# receiver_mini_rfm95.net
KiCad netlist of a schematic drawn in EAGLE
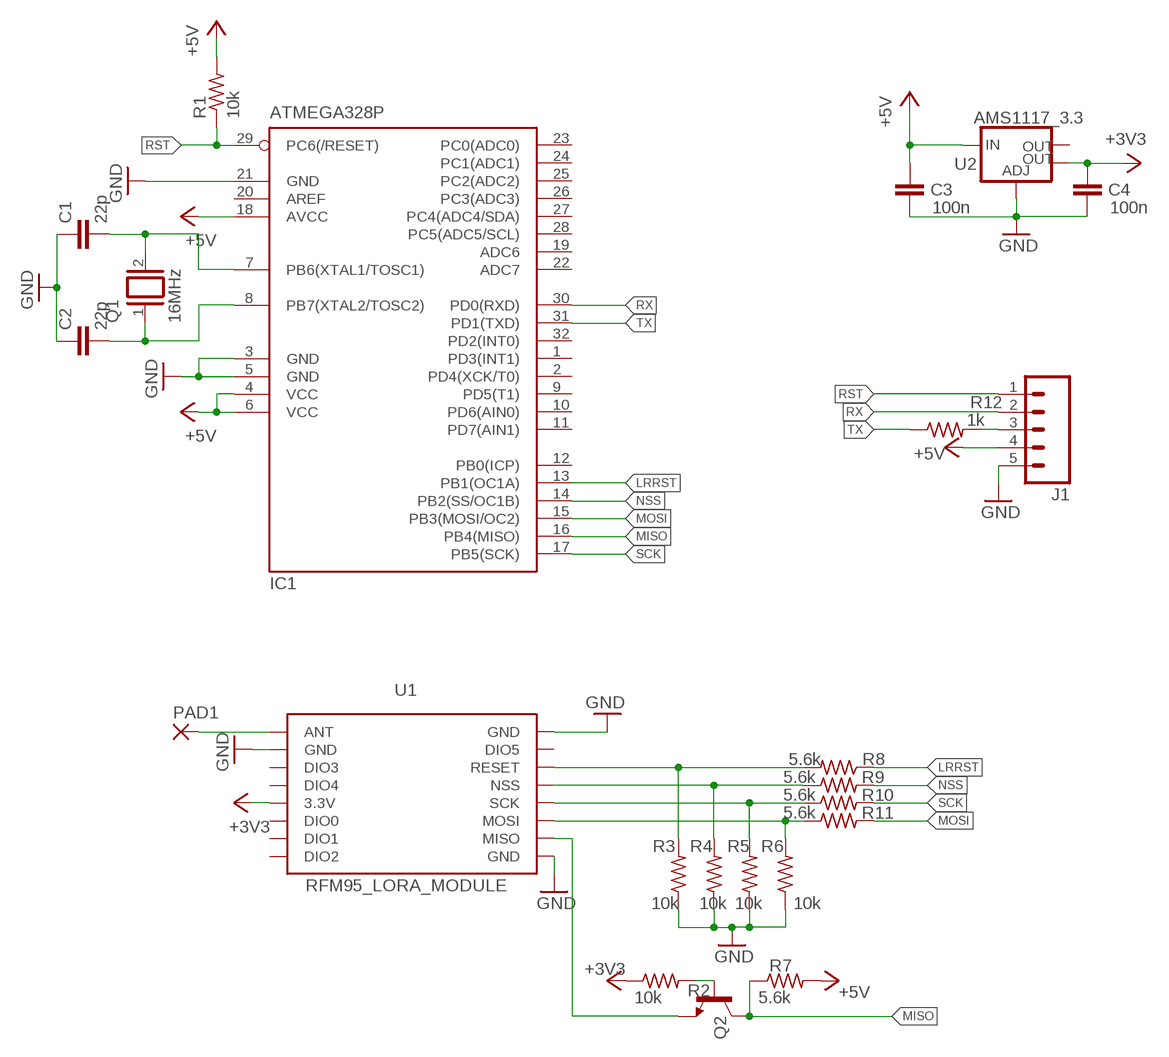
[diagram p0: schematic, sheet 1]

(export (version "E")
  (design (tool "Eeschema 10.0.6"))
  (components
    (comp (ref "C1")
      (value "22p")
      (footprint "eagle-import:C0805K")
      (libsource (lib "eagle-import") (part "C-EUC0805K"))
    )
    (comp (ref "C2")
      (value "22p")
      (footprint "eagle-import:C0805K")
      (libsource (lib "eagle-import") (part "C-EUC0805K"))
    )
    (comp (ref "C3")
      (value "100n")
      (footprint "eagle-import:C0805K")
      (libsource (lib "eagle-import") (part "C-EUC0805K"))
    )
    (comp (ref "C4")
      (value "100n")
      (footprint "eagle-import:C0805K")
      (libsource (lib "eagle-import") (part "C-EUC0805K"))
    )
    (comp (ref "IC1")
      (value "ATMEGA328P")
      (footprint "eagle-import:TQFP32-08")
      (fields (field (name "MPN") "ATMEGA8-16AU"))
      (libsource (lib "eagle-import") (part "MEGA8-AI"))
    )
    (comp (ref "J1")
      (value "M05PTH")
      (footprint "eagle-import:1X05")
      (libsource (lib "eagle-import") (part "M05PTH"))
    )
    (comp (ref "PAD1")
      (value "2,15/1,0")
      (footprint "eagle-import:2,15_1,0")
      (libsource (lib "eagle-import") (part "2,15/1,0"))
    )
    (comp (ref "Q1")
      (value "16MHz")
      (footprint "eagle-import:QS")
      (libsource (lib "eagle-import") (part "XTAL/S"))
    )
    (comp (ref "Q2")
      (value "BC817-16SMD")
      (footprint "eagle-import:SOT23-BEC")
      (libsource (lib "eagle-import") (part "BC817SMD-16"))
    )
    (comp (ref "R1")
      (value "10k")
      (footprint "eagle-import:R0805")
      (libsource (lib "eagle-import") (part "R-US_R0805"))
    )
    (comp (ref "R2")
      (value "10k")
      (footprint "eagle-import:R0805")
      (libsource (lib "eagle-import") (part "R-US_R0805"))
    )
    (comp (ref "R3")
      (value "10k")
      (footprint "eagle-import:R0805")
      (libsource (lib "eagle-import") (part "R-US_R0805"))
    )
    (comp (ref "R4")
      (value "10k")
      (footprint "eagle-import:R0805")
      (libsource (lib "eagle-import") (part "R-US_R0805"))
    )
    (comp (ref "R5")
      (value "10k")
      (footprint "eagle-import:R0805")
      (libsource (lib "eagle-import") (part "R-US_R0805"))
    )
    (comp (ref "R6")
      (value "10k")
      (footprint "eagle-import:R0805")
      (libsource (lib "eagle-import") (part "R-US_R0805"))
    )
    (comp (ref "R7")
      (value "5.6k")
      (footprint "eagle-import:R0805")
      (libsource (lib "eagle-import") (part "R-US_R0805"))
    )
    (comp (ref "R8")
      (value "5.6k")
      (footprint "eagle-import:R0805")
      (libsource (lib "eagle-import") (part "R-US_R0805"))
    )
    (comp (ref "R9")
      (value "5.6k")
      (footprint "eagle-import:R0805")
      (libsource (lib "eagle-import") (part "R-US_R0805"))
    )
    (comp (ref "R10")
      (value "5.6k")
      (footprint "eagle-import:R0805")
      (libsource (lib "eagle-import") (part "R-US_R0805"))
    )
    (comp (ref "R11")
      (value "5.6k")
      (footprint "eagle-import:R0805")
      (libsource (lib "eagle-import") (part "R-US_R0805"))
    )
    (comp (ref "R12")
      (value "1k")
      (footprint "eagle-import:R0805")
      (libsource (lib "eagle-import") (part "R-US_R0805"))
    )
    (comp (ref "U1")
      (value "RFM95_LORA_MODULE")
      (footprint "eagle-import:RFM95")
      (libsource (lib "eagle-import") (part "RFM95_LORA_MODULE"))
    )
    (comp (ref "U2")
      (value "AMS1117_3.3")
      (footprint "eagle-import:SOT223")
      (libsource (lib "eagle-import") (part "V_REG_LM1117SOT223"))
    )
  )
  (nets
    (net (code "1") (name "+3V3") (class "Default")
      (node (ref "C4") (pin "2") (pinfunction "2_2") (pintype "passive"))
      (node (ref "R2") (pin "1") (pinfunction "1_1") (pintype "passive"))
      (node (ref "U1") (pin "3.3V") (pinfunction "3.3V_3.3V") (pintype "bidirectional"))
      (node (ref "U2") (pin "4") (pinfunction "OUT_4") (pintype "output"))
    )
    (net (code "2") (name "+5V") (class "Default")
      (node (ref "C3") (pin "2") (pinfunction "2_2") (pintype "passive"))
      (node (ref "IC1") (pin "18") (pinfunction "AVCC_18") (pintype "power_in"))
      (node (ref "IC1") (pin "4") (pinfunction "VCC_4") (pintype "power_in"))
      (node (ref "IC1") (pin "6") (pinfunction "VCC_6") (pintype "power_in"))
      (node (ref "J1") (pin "4") (pinfunction "4_4") (pintype "passive"))
      (node (ref "R1") (pin "2") (pinfunction "2_2") (pintype "passive"))
      (node (ref "R7") (pin "2") (pinfunction "2_2") (pintype "passive"))
      (node (ref "U2") (pin "3") (pinfunction "IN_3") (pintype "input"))
    )
    (net (code "3") (name "/DIO3") (class "Default")
      (node (ref "U1") (pin "DIO3") (pinfunction "DIO3_DIO3") (pintype "power_in"))
    )
    (net (code "4") (name "GND") (class "Default")
      (node (ref "C1") (pin "1") (pinfunction "1_1") (pintype "passive"))
      (node (ref "C2") (pin "1") (pinfunction "1_1") (pintype "passive"))
      (node (ref "C3") (pin "1") (pinfunction "1_1") (pintype "passive"))
      (node (ref "C4") (pin "1") (pinfunction "1_1") (pintype "passive"))
      (node (ref "IC1") (pin "21") (pinfunction "GND_21") (pintype "power_in"))
      (node (ref "IC1") (pin "3") (pinfunction "GND_3") (pintype "power_in"))
      (node (ref "IC1") (pin "5") (pinfunction "GND_5") (pintype "power_in"))
      (node (ref "J1") (pin "5") (pinfunction "5_5") (pintype "passive"))
      (node (ref "R3") (pin "1") (pinfunction "1_1") (pintype "passive"))
      (node (ref "R4") (pin "1") (pinfunction "1_1") (pintype "passive"))
      (node (ref "R5") (pin "1") (pinfunction "1_1") (pintype "passive"))
      (node (ref "R6") (pin "1") (pinfunction "1_1") (pintype "passive"))
      (node (ref "U1") (pin "GND") (pinfunction "GND_GND") (pintype "power_in"))
      (node (ref "U1") (pin "GND@1") (pinfunction "GND_GND@1") (pintype "power_in"))
      (node (ref "U1") (pin "GND@2") (pinfunction "GND_GND@2") (pintype "power_in"))
      (node (ref "U2") (pin "1") (pinfunction "ADJ_1") (pintype "input"))
    )
    (net (code "5") (name "LRRST") (class "Default")
      (node (ref "IC1") (pin "13") (pinfunction "PB1(OC1A)_13") (pintype "bidirectional"))
      (node (ref "R8") (pin "1") (pinfunction "1_1") (pintype "passive"))
    )
    (net (code "6") (name "MISO") (class "Default")
      (node (ref "IC1") (pin "16") (pinfunction "PB4(MISO)_16") (pintype "bidirectional"))
      (node (ref "Q2") (pin "C") (pinfunction "C_C") (pintype "passive"))
      (node (ref "R7") (pin "1") (pinfunction "1_1") (pintype "passive"))
    )
    (net (code "7") (name "MOSI") (class "Default")
      (node (ref "IC1") (pin "15") (pinfunction "PB3(MOSI/OC2)_15") (pintype "bidirectional"))
      (node (ref "R11") (pin "2") (pinfunction "2_2") (pintype "passive"))
    )
    (net (code "8") (name "NSS") (class "Default")
      (node (ref "IC1") (pin "14") (pinfunction "PB2(SS/OC1B)_14") (pintype "bidirectional"))
      (node (ref "R9") (pin "2") (pinfunction "2_2") (pintype "passive"))
    )
    (net (code "9") (name "Net-(IC1-PB6(XTAL1{slash}TOSC1))") (class "Default")
      (node (ref "C1") (pin "2") (pinfunction "2_2") (pintype "passive"))
      (node (ref "IC1") (pin "7") (pinfunction "PB6(XTAL1/TOSC1)_7") (pintype "bidirectional"))
      (node (ref "Q1") (pin "2") (pinfunction "2_2") (pintype "passive"))
    )
    (net (code "10") (name "Net-(IC1-PB7(XTAL2{slash}TOSC2))") (class "Default")
      (node (ref "C2") (pin "2") (pinfunction "2_2") (pintype "passive"))
      (node (ref "IC1") (pin "8") (pinfunction "PB7(XTAL2/TOSC2)_8") (pintype "bidirectional"))
      (node (ref "Q1") (pin "1") (pinfunction "1_1") (pintype "passive"))
    )
    (net (code "11") (name "Net-(J1-Pad3)") (class "Default")
      (node (ref "J1") (pin "3") (pinfunction "3_3") (pintype "passive"))
      (node (ref "R12") (pin "2") (pinfunction "2_2") (pintype "passive"))
    )
    (net (code "12") (name "Net-(PAD1-P)") (class "Default")
      (node (ref "PAD1") (pin "1") (pinfunction "P_1") (pintype "passive"))
      (node (ref "U1") (pin "ANT") (pinfunction "ANT_ANT") (pintype "power_in"))
    )
    (net (code "13") (name "Net-(Q2-PadB)") (class "Default")
      (node (ref "Q2") (pin "B") (pinfunction "B_B") (pintype "passive"))
      (node (ref "R2") (pin "2") (pinfunction "2_2") (pintype "passive"))
    )
    (net (code "14") (name "Net-(Q2-PadE)") (class "Default")
      (node (ref "Q2") (pin "E") (pinfunction "E_E") (pintype "passive"))
      (node (ref "U1") (pin "MISO") (pinfunction "MISO_MISO") (pintype "bidirectional"))
    )
    (net (code "15") (name "Net-(R3-Pad2)") (class "Default")
      (node (ref "R3") (pin "2") (pinfunction "2_2") (pintype "passive"))
      (node (ref "R8") (pin "2") (pinfunction "2_2") (pintype "passive"))
      (node (ref "U1") (pin "RESET") (pinfunction "RESET_RESET") (pintype "bidirectional"))
    )
    (net (code "16") (name "Net-(R4-Pad2)") (class "Default")
      (node (ref "R4") (pin "2") (pinfunction "2_2") (pintype "passive"))
      (node (ref "R9") (pin "1") (pinfunction "1_1") (pintype "passive"))
      (node (ref "U1") (pin "NSS") (pinfunction "NSS_NSS") (pintype "bidirectional"))
    )
    (net (code "17") (name "Net-(R10-Pad1)") (class "Default")
      (node (ref "R10") (pin "1") (pinfunction "1_1") (pintype "passive"))
      (node (ref "R5") (pin "2") (pinfunction "2_2") (pintype "passive"))
      (node (ref "U1") (pin "SCK") (pinfunction "SCK_SCK") (pintype "bidirectional"))
    )
    (net (code "18") (name "Net-(R11-Pad1)") (class "Default")
      (node (ref "R11") (pin "1") (pinfunction "1_1") (pintype "passive"))
      (node (ref "R6") (pin "2") (pinfunction "2_2") (pintype "passive"))
      (node (ref "U1") (pin "MOSI") (pinfunction "MOSI_MOSI") (pintype "bidirectional"))
    )
    (net (code "19") (name "RST") (class "Default")
      (node (ref "IC1") (pin "29") (pinfunction "PC6(/RESET)_29") (pintype "bidirectional"))
      (node (ref "J1") (pin "1") (pinfunction "1_1") (pintype "passive"))
      (node (ref "R1") (pin "1") (pinfunction "1_1") (pintype "passive"))
    )
    (net (code "20") (name "RX") (class "Default")
      (node (ref "IC1") (pin "30") (pinfunction "PD0(RXD)_30") (pintype "bidirectional"))
      (node (ref "J1") (pin "2") (pinfunction "2_2") (pintype "passive"))
    )
    (net (code "21") (name "SCK") (class "Default")
      (node (ref "IC1") (pin "17") (pinfunction "PB5(SCK)_17") (pintype "bidirectional"))
      (node (ref "R10") (pin "2") (pinfunction "2_2") (pintype "passive"))
    )
    (net (code "22") (name "TX") (class "Default")
      (node (ref "IC1") (pin "31") (pinfunction "PD1(TXD)_31") (pintype "bidirectional"))
      (node (ref "R12") (pin "1") (pinfunction "1_1") (pintype "passive"))
    )
    (net (code "23") (name "unconnected-(IC1-ADC6-Pad19)") (class "Default")
      (node (ref "IC1") (pin "19") (pinfunction "ADC6_19") (pintype "bidirectional"))
    )
    (net (code "24") (name "unconnected-(IC1-ADC7-Pad22)") (class "Default")
      (node (ref "IC1") (pin "22") (pinfunction "ADC7_22") (pintype "bidirectional"))
    )
    (net (code "25") (name "unconnected-(IC1-AREF-Pad20)") (class "Default")
      (node (ref "IC1") (pin "20") (pinfunction "AREF_20") (pintype "passive"))
    )
    (net (code "26") (name "unconnected-(IC1-PB0(ICP)-Pad12)") (class "Default")
      (node (ref "IC1") (pin "12") (pinfunction "PB0(ICP)_12") (pintype "bidirectional"))
    )
    (net (code "27") (name "unconnected-(IC1-PC0(ADC0)-Pad23)") (class "Default")
      (node (ref "IC1") (pin "23") (pinfunction "PC0(ADC0)_23") (pintype "bidirectional"))
    )
    (net (code "28") (name "unconnected-(IC1-PC1(ADC1)-Pad24)") (class "Default")
      (node (ref "IC1") (pin "24") (pinfunction "PC1(ADC1)_24") (pintype "bidirectional"))
    )
    (net (code "29") (name "unconnected-(IC1-PC2(ADC2)-Pad25)") (class "Default")
      (node (ref "IC1") (pin "25") (pinfunction "PC2(ADC2)_25") (pintype "bidirectional"))
    )
    (net (code "30") (name "unconnected-(IC1-PC3(ADC3)-Pad26)") (class "Default")
      (node (ref "IC1") (pin "26") (pinfunction "PC3(ADC3)_26") (pintype "bidirectional"))
    )
    (net (code "31") (name "unconnected-(IC1-PC4(ADC4{slash}SDA)-Pad27)") (class "Default")
      (node (ref "IC1") (pin "27") (pinfunction "PC4(ADC4/SDA)_27") (pintype "bidirectional"))
    )
    (net (code "32") (name "unconnected-(IC1-PC5(ADC5{slash}SCL)-Pad28)") (class "Default")
      (node (ref "IC1") (pin "28") (pinfunction "PC5(ADC5/SCL)_28") (pintype "bidirectional"))
    )
    (net (code "33") (name "unconnected-(IC1-PD2(INT0)-Pad32)") (class "Default")
      (node (ref "IC1") (pin "32") (pinfunction "PD2(INT0)_32") (pintype "bidirectional"))
    )
    (net (code "34") (name "unconnected-(IC1-PD3(INT1)-Pad1)") (class "Default")
      (node (ref "IC1") (pin "1") (pinfunction "PD3(INT1)_1") (pintype "bidirectional"))
    )
    (net (code "35") (name "unconnected-(IC1-PD4(XCK{slash}T0)-Pad2)") (class "Default")
      (node (ref "IC1") (pin "2") (pinfunction "PD4(XCK/T0)_2") (pintype "bidirectional"))
    )
    (net (code "36") (name "unconnected-(IC1-PD5(T1)-Pad9)") (class "Default")
      (node (ref "IC1") (pin "9") (pinfunction "PD5(T1)_9") (pintype "bidirectional"))
    )
    (net (code "37") (name "unconnected-(IC1-PD6(AIN0)-Pad10)") (class "Default")
      (node (ref "IC1") (pin "10") (pinfunction "PD6(AIN0)_10") (pintype "bidirectional"))
    )
    (net (code "38") (name "unconnected-(IC1-PD7(AIN1)-Pad11)") (class "Default")
      (node (ref "IC1") (pin "11") (pinfunction "PD7(AIN1)_11") (pintype "bidirectional"))
    )
    (net (code "39") (name "unconnected-(U1-PadDIO0)") (class "Default")
      (node (ref "U1") (pin "DIO0") (pinfunction "DIO0_DIO0") (pintype "bidirectional"))
    )
    (net (code "40") (name "unconnected-(U1-PadDIO1)") (class "Default")
      (node (ref "U1") (pin "DIO1") (pinfunction "DIO1_DIO1") (pintype "bidirectional"))
    )
    (net (code "41") (name "unconnected-(U1-PadDIO2)") (class "Default")
      (node (ref "U1") (pin "DIO2") (pinfunction "DIO2_DIO2") (pintype "bidirectional"))
    )
    (net (code "42") (name "unconnected-(U1-PadDIO4)") (class "Default")
      (node (ref "U1") (pin "DIO4") (pinfunction "DIO4_DIO4") (pintype "bidirectional"))
    )
    (net (code "43") (name "unconnected-(U1-PadDIO5)") (class "Default")
      (node (ref "U1") (pin "DIO5") (pinfunction "DIO5_DIO5") (pintype "bidirectional"))
    )
    (net (code "44") (name "unconnected-(U2-OUT-Pad2)") (class "Default")
      (node (ref "U2") (pin "2") (pinfunction "OUT_2") (pintype "output"))
    )
  )
)
